# SLT3-PAY-1Q2T_P2.net
KiCad netlist of a schematic drawn in Altium Designer
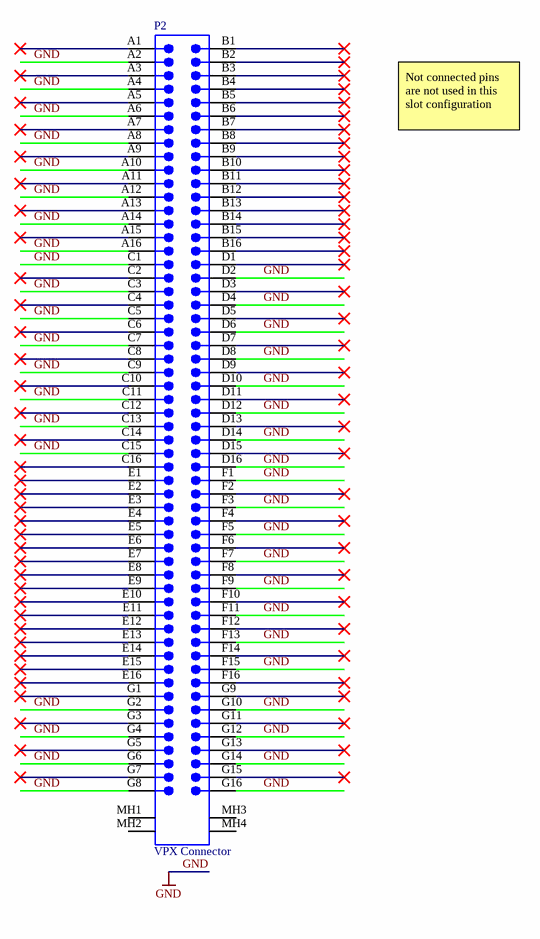
[diagram p0: SLT3-PAY-1Q2T_P2.SchDoc]

(export (version "E")
  (design (tool "Eeschema 10.0.6"))
  (components
    (comp (ref "P2")
      (value "VPX Connector")
      (footprint "BTB1-8-4H112M")
      (description "Ruggedized Board-to-Board Connector, Right Angle, 7-Row, Pitch 1.8mm, 112-Position")
      (fields (field (name "MANUFACTURER") "TE") (field (name "MANUFACTURER PART NUMBER") "2102771-1"))
      (libsource (lib "SVPX") (part "2102771-1"))
    )
  )
  (nets
    (net (code "1") (name "GND") (class "Default")
      (node (ref "P2") (pin "A10") (pinfunction "A10_A10") (pintype "passive"))
      (node (ref "P2") (pin "A12") (pinfunction "A12_A12") (pintype "passive"))
      (node (ref "P2") (pin "A14") (pinfunction "A14_A14") (pintype "passive"))
      (node (ref "P2") (pin "A16") (pinfunction "A16_A16") (pintype "passive"))
      (node (ref "P2") (pin "A2") (pinfunction "A2_A2") (pintype "passive"))
      (node (ref "P2") (pin "A4") (pinfunction "A4_A4") (pintype "passive"))
      (node (ref "P2") (pin "A6") (pinfunction "A6_A6") (pintype "passive"))
      (node (ref "P2") (pin "A8") (pinfunction "A8_A8") (pintype "passive"))
      (node (ref "P2") (pin "C1") (pinfunction "C1_C1") (pintype "passive"))
      (node (ref "P2") (pin "C11") (pinfunction "C11_C11") (pintype "passive"))
      (node (ref "P2") (pin "C13") (pinfunction "C13_C13") (pintype "passive"))
      (node (ref "P2") (pin "C15") (pinfunction "C15_C15") (pintype "passive"))
      (node (ref "P2") (pin "C3") (pinfunction "C3_C3") (pintype "passive"))
      (node (ref "P2") (pin "C5") (pinfunction "C5_C5") (pintype "passive"))
      (node (ref "P2") (pin "C7") (pinfunction "C7_C7") (pintype "passive"))
      (node (ref "P2") (pin "C9") (pinfunction "C9_C9") (pintype "passive"))
      (node (ref "P2") (pin "D10") (pinfunction "D10_D10") (pintype "passive"))
      (node (ref "P2") (pin "D12") (pinfunction "D12_D12") (pintype "passive"))
      (node (ref "P2") (pin "D14") (pinfunction "D14_D14") (pintype "passive"))
      (node (ref "P2") (pin "D16") (pinfunction "D16_D16") (pintype "passive"))
      (node (ref "P2") (pin "D2") (pinfunction "D2_D2") (pintype "passive"))
      (node (ref "P2") (pin "D4") (pinfunction "D4_D4") (pintype "passive"))
      (node (ref "P2") (pin "D6") (pinfunction "D6_D6") (pintype "passive"))
      (node (ref "P2") (pin "D8") (pinfunction "D8_D8") (pintype "passive"))
      (node (ref "P2") (pin "F1") (pinfunction "F1_F1") (pintype "passive"))
      (node (ref "P2") (pin "F11") (pinfunction "F11_F11") (pintype "passive"))
      (node (ref "P2") (pin "F13") (pinfunction "F13_F13") (pintype "passive"))
      (node (ref "P2") (pin "F15") (pinfunction "F15_F15") (pintype "passive"))
      (node (ref "P2") (pin "F3") (pinfunction "F3_F3") (pintype "passive"))
      (node (ref "P2") (pin "F5") (pinfunction "F5_F5") (pintype "passive"))
      (node (ref "P2") (pin "F7") (pinfunction "F7_F7") (pintype "passive"))
      (node (ref "P2") (pin "F9") (pinfunction "F9_F9") (pintype "passive"))
      (node (ref "P2") (pin "G10") (pinfunction "G10_G10") (pintype "passive"))
      (node (ref "P2") (pin "G12") (pinfunction "G12_G12") (pintype "passive"))
      (node (ref "P2") (pin "G14") (pinfunction "G14_G14") (pintype "passive"))
      (node (ref "P2") (pin "G16") (pinfunction "G16_G16") (pintype "passive"))
      (node (ref "P2") (pin "G2") (pinfunction "G2_G2") (pintype "passive"))
      (node (ref "P2") (pin "G4") (pinfunction "G4_G4") (pintype "passive"))
      (node (ref "P2") (pin "G6") (pinfunction "G6_G6") (pintype "passive"))
      (node (ref "P2") (pin "G8") (pinfunction "G8_G8") (pintype "passive"))
    )
    (net (code "2") (name "unconnected-(P2-PadA1)") (class "Default")
      (node (ref "P2") (pin "A1") (pinfunction "A1_A1") (pintype "passive+no_connect"))
    )
    (net (code "3") (name "unconnected-(P2-PadA3)") (class "Default")
      (node (ref "P2") (pin "A3") (pinfunction "A3_A3") (pintype "passive+no_connect"))
    )
    (net (code "4") (name "unconnected-(P2-PadA5)") (class "Default")
      (node (ref "P2") (pin "A5") (pinfunction "A5_A5") (pintype "passive+no_connect"))
    )
    (net (code "5") (name "unconnected-(P2-PadA7)") (class "Default")
      (node (ref "P2") (pin "A7") (pinfunction "A7_A7") (pintype "passive+no_connect"))
    )
    (net (code "6") (name "unconnected-(P2-PadA9)") (class "Default")
      (node (ref "P2") (pin "A9") (pinfunction "A9_A9") (pintype "passive+no_connect"))
    )
    (net (code "7") (name "unconnected-(P2-PadA11)") (class "Default")
      (node (ref "P2") (pin "A11") (pinfunction "A11_A11") (pintype "passive+no_connect"))
    )
    (net (code "8") (name "unconnected-(P2-PadA13)") (class "Default")
      (node (ref "P2") (pin "A13") (pinfunction "A13_A13") (pintype "passive+no_connect"))
    )
    (net (code "9") (name "unconnected-(P2-PadA15)") (class "Default")
      (node (ref "P2") (pin "A15") (pinfunction "A15_A15") (pintype "passive+no_connect"))
    )
    (net (code "10") (name "unconnected-(P2-PadB1)") (class "Default")
      (node (ref "P2") (pin "B1") (pinfunction "B1_B1") (pintype "passive+no_connect"))
    )
    (net (code "11") (name "unconnected-(P2-PadB2)") (class "Default")
      (node (ref "P2") (pin "B2") (pinfunction "B2_B2") (pintype "passive+no_connect"))
    )
    (net (code "12") (name "unconnected-(P2-PadB3)") (class "Default")
      (node (ref "P2") (pin "B3") (pinfunction "B3_B3") (pintype "passive+no_connect"))
    )
    (net (code "13") (name "unconnected-(P2-PadB4)") (class "Default")
      (node (ref "P2") (pin "B4") (pinfunction "B4_B4") (pintype "passive+no_connect"))
    )
    (net (code "14") (name "unconnected-(P2-PadB5)") (class "Default")
      (node (ref "P2") (pin "B5") (pinfunction "B5_B5") (pintype "passive+no_connect"))
    )
    (net (code "15") (name "unconnected-(P2-PadB6)") (class "Default")
      (node (ref "P2") (pin "B6") (pinfunction "B6_B6") (pintype "passive+no_connect"))
    )
    (net (code "16") (name "unconnected-(P2-PadB7)") (class "Default")
      (node (ref "P2") (pin "B7") (pinfunction "B7_B7") (pintype "passive+no_connect"))
    )
    (net (code "17") (name "unconnected-(P2-PadB8)") (class "Default")
      (node (ref "P2") (pin "B8") (pinfunction "B8_B8") (pintype "passive+no_connect"))
    )
    (net (code "18") (name "unconnected-(P2-PadB9)") (class "Default")
      (node (ref "P2") (pin "B9") (pinfunction "B9_B9") (pintype "passive+no_connect"))
    )
    (net (code "19") (name "unconnected-(P2-PadB10)") (class "Default")
      (node (ref "P2") (pin "B10") (pinfunction "B10_B10") (pintype "passive+no_connect"))
    )
    (net (code "20") (name "unconnected-(P2-PadB11)") (class "Default")
      (node (ref "P2") (pin "B11") (pinfunction "B11_B11") (pintype "passive+no_connect"))
    )
    (net (code "21") (name "unconnected-(P2-PadB12)") (class "Default")
      (node (ref "P2") (pin "B12") (pinfunction "B12_B12") (pintype "passive+no_connect"))
    )
    (net (code "22") (name "unconnected-(P2-PadB13)") (class "Default")
      (node (ref "P2") (pin "B13") (pinfunction "B13_B13") (pintype "passive+no_connect"))
    )
    (net (code "23") (name "unconnected-(P2-PadB14)") (class "Default")
      (node (ref "P2") (pin "B14") (pinfunction "B14_B14") (pintype "passive+no_connect"))
    )
    (net (code "24") (name "unconnected-(P2-PadB15)") (class "Default")
      (node (ref "P2") (pin "B15") (pinfunction "B15_B15") (pintype "passive+no_connect"))
    )
    (net (code "25") (name "unconnected-(P2-PadB16)") (class "Default")
      (node (ref "P2") (pin "B16") (pinfunction "B16_B16") (pintype "passive+no_connect"))
    )
    (net (code "26") (name "unconnected-(P2-PadC2)") (class "Default")
      (node (ref "P2") (pin "C2") (pinfunction "C2_C2") (pintype "passive+no_connect"))
    )
    (net (code "27") (name "unconnected-(P2-PadC4)") (class "Default")
      (node (ref "P2") (pin "C4") (pinfunction "C4_C4") (pintype "passive+no_connect"))
    )
    (net (code "28") (name "unconnected-(P2-PadC6)") (class "Default")
      (node (ref "P2") (pin "C6") (pinfunction "C6_C6") (pintype "passive+no_connect"))
    )
    (net (code "29") (name "unconnected-(P2-PadC8)") (class "Default")
      (node (ref "P2") (pin "C8") (pinfunction "C8_C8") (pintype "passive+no_connect"))
    )
    (net (code "30") (name "unconnected-(P2-PadC10)") (class "Default")
      (node (ref "P2") (pin "C10") (pinfunction "C10_C10") (pintype "passive+no_connect"))
    )
    (net (code "31") (name "unconnected-(P2-PadC12)") (class "Default")
      (node (ref "P2") (pin "C12") (pinfunction "C12_C12") (pintype "passive+no_connect"))
    )
    (net (code "32") (name "unconnected-(P2-PadC14)") (class "Default")
      (node (ref "P2") (pin "C14") (pinfunction "C14_C14") (pintype "passive+no_connect"))
    )
    (net (code "33") (name "unconnected-(P2-PadC16)") (class "Default")
      (node (ref "P2") (pin "C16") (pinfunction "C16_C16") (pintype "passive+no_connect"))
    )
    (net (code "34") (name "unconnected-(P2-PadD1)") (class "Default")
      (node (ref "P2") (pin "D1") (pinfunction "D1_D1") (pintype "passive+no_connect"))
    )
    (net (code "35") (name "unconnected-(P2-PadD3)") (class "Default")
      (node (ref "P2") (pin "D3") (pinfunction "D3_D3") (pintype "passive+no_connect"))
    )
    (net (code "36") (name "unconnected-(P2-PadD5)") (class "Default")
      (node (ref "P2") (pin "D5") (pinfunction "D5_D5") (pintype "passive+no_connect"))
    )
    (net (code "37") (name "unconnected-(P2-PadD7)") (class "Default")
      (node (ref "P2") (pin "D7") (pinfunction "D7_D7") (pintype "passive+no_connect"))
    )
    (net (code "38") (name "unconnected-(P2-PadD9)") (class "Default")
      (node (ref "P2") (pin "D9") (pinfunction "D9_D9") (pintype "passive+no_connect"))
    )
    (net (code "39") (name "unconnected-(P2-PadD11)") (class "Default")
      (node (ref "P2") (pin "D11") (pinfunction "D11_D11") (pintype "passive+no_connect"))
    )
    (net (code "40") (name "unconnected-(P2-PadD13)") (class "Default")
      (node (ref "P2") (pin "D13") (pinfunction "D13_D13") (pintype "passive+no_connect"))
    )
    (net (code "41") (name "unconnected-(P2-PadD15)") (class "Default")
      (node (ref "P2") (pin "D15") (pinfunction "D15_D15") (pintype "passive+no_connect"))
    )
    (net (code "42") (name "unconnected-(P2-PadE1)") (class "Default")
      (node (ref "P2") (pin "E1") (pinfunction "E1_E1") (pintype "passive+no_connect"))
    )
    (net (code "43") (name "unconnected-(P2-PadE2)") (class "Default")
      (node (ref "P2") (pin "E2") (pinfunction "E2_E2") (pintype "passive+no_connect"))
    )
    (net (code "44") (name "unconnected-(P2-PadE3)") (class "Default")
      (node (ref "P2") (pin "E3") (pinfunction "E3_E3") (pintype "passive+no_connect"))
    )
    (net (code "45") (name "unconnected-(P2-PadE4)") (class "Default")
      (node (ref "P2") (pin "E4") (pinfunction "E4_E4") (pintype "passive+no_connect"))
    )
    (net (code "46") (name "unconnected-(P2-PadE5)") (class "Default")
      (node (ref "P2") (pin "E5") (pinfunction "E5_E5") (pintype "passive+no_connect"))
    )
    (net (code "47") (name "unconnected-(P2-PadE6)") (class "Default")
      (node (ref "P2") (pin "E6") (pinfunction "E6_E6") (pintype "passive+no_connect"))
    )
    (net (code "48") (name "unconnected-(P2-PadE7)") (class "Default")
      (node (ref "P2") (pin "E7") (pinfunction "E7_E7") (pintype "passive+no_connect"))
    )
    (net (code "49") (name "unconnected-(P2-PadE8)") (class "Default")
      (node (ref "P2") (pin "E8") (pinfunction "E8_E8") (pintype "passive+no_connect"))
    )
    (net (code "50") (name "unconnected-(P2-PadE9)") (class "Default")
      (node (ref "P2") (pin "E9") (pinfunction "E9_E9") (pintype "passive+no_connect"))
    )
    (net (code "51") (name "unconnected-(P2-PadE10)") (class "Default")
      (node (ref "P2") (pin "E10") (pinfunction "E10_E10") (pintype "passive+no_connect"))
    )
    (net (code "52") (name "unconnected-(P2-PadE11)") (class "Default")
      (node (ref "P2") (pin "E11") (pinfunction "E11_E11") (pintype "passive+no_connect"))
    )
    (net (code "53") (name "unconnected-(P2-PadE12)") (class "Default")
      (node (ref "P2") (pin "E12") (pinfunction "E12_E12") (pintype "passive+no_connect"))
    )
    (net (code "54") (name "unconnected-(P2-PadE13)") (class "Default")
      (node (ref "P2") (pin "E13") (pinfunction "E13_E13") (pintype "passive+no_connect"))
    )
    (net (code "55") (name "unconnected-(P2-PadE14)") (class "Default")
      (node (ref "P2") (pin "E14") (pinfunction "E14_E14") (pintype "passive+no_connect"))
    )
    (net (code "56") (name "unconnected-(P2-PadE15)") (class "Default")
      (node (ref "P2") (pin "E15") (pinfunction "E15_E15") (pintype "passive+no_connect"))
    )
    (net (code "57") (name "unconnected-(P2-PadE16)") (class "Default")
      (node (ref "P2") (pin "E16") (pinfunction "E16_E16") (pintype "passive+no_connect"))
    )
    (net (code "58") (name "unconnected-(P2-PadF2)") (class "Default")
      (node (ref "P2") (pin "F2") (pinfunction "F2_F2") (pintype "passive+no_connect"))
    )
    (net (code "59") (name "unconnected-(P2-PadF4)") (class "Default")
      (node (ref "P2") (pin "F4") (pinfunction "F4_F4") (pintype "passive+no_connect"))
    )
    (net (code "60") (name "unconnected-(P2-PadF6)") (class "Default")
      (node (ref "P2") (pin "F6") (pinfunction "F6_F6") (pintype "passive+no_connect"))
    )
    (net (code "61") (name "unconnected-(P2-PadF8)") (class "Default")
      (node (ref "P2") (pin "F8") (pinfunction "F8_F8") (pintype "passive+no_connect"))
    )
    (net (code "62") (name "unconnected-(P2-PadF10)") (class "Default")
      (node (ref "P2") (pin "F10") (pinfunction "F10_F10") (pintype "passive+no_connect"))
    )
    (net (code "63") (name "unconnected-(P2-PadF12)") (class "Default")
      (node (ref "P2") (pin "F12") (pinfunction "F12_F12") (pintype "passive+no_connect"))
    )
    (net (code "64") (name "unconnected-(P2-PadF14)") (class "Default")
      (node (ref "P2") (pin "F14") (pinfunction "F14_F14") (pintype "passive+no_connect"))
    )
    (net (code "65") (name "unconnected-(P2-PadF16)") (class "Default")
      (node (ref "P2") (pin "F16") (pinfunction "F16_F16") (pintype "passive+no_connect"))
    )
    (net (code "66") (name "unconnected-(P2-PadG1)") (class "Default")
      (node (ref "P2") (pin "G1") (pinfunction "G1_G1") (pintype "passive+no_connect"))
    )
    (net (code "67") (name "unconnected-(P2-PadG3)") (class "Default")
      (node (ref "P2") (pin "G3") (pinfunction "G3_G3") (pintype "passive+no_connect"))
    )
    (net (code "68") (name "unconnected-(P2-PadG5)") (class "Default")
      (node (ref "P2") (pin "G5") (pinfunction "G5_G5") (pintype "passive+no_connect"))
    )
    (net (code "69") (name "unconnected-(P2-PadG7)") (class "Default")
      (node (ref "P2") (pin "G7") (pinfunction "G7_G7") (pintype "passive+no_connect"))
    )
    (net (code "70") (name "unconnected-(P2-PadG9)") (class "Default")
      (node (ref "P2") (pin "G9") (pinfunction "G9_G9") (pintype "passive+no_connect"))
    )
    (net (code "71") (name "unconnected-(P2-PadG11)") (class "Default")
      (node (ref "P2") (pin "G11") (pinfunction "G11_G11") (pintype "passive+no_connect"))
    )
    (net (code "72") (name "unconnected-(P2-PadG13)") (class "Default")
      (node (ref "P2") (pin "G13") (pinfunction "G13_G13") (pintype "passive+no_connect"))
    )
    (net (code "73") (name "unconnected-(P2-PadG15)") (class "Default")
      (node (ref "P2") (pin "G15") (pinfunction "G15_G15") (pintype "passive+no_connect"))
    )
    (net (code "74") (name "unconnected-(P2-PadMH1)") (class "Default")
      (node (ref "P2") (pin "MH1") (pinfunction "MH1_MH1") (pintype "passive"))
    )
    (net (code "75") (name "unconnected-(P2-PadMH2)") (class "Default")
      (node (ref "P2") (pin "MH2") (pinfunction "MH2_MH2") (pintype "passive"))
    )
    (net (code "76") (name "unconnected-(P2-PadMH3)") (class "Default")
      (node (ref "P2") (pin "MH3") (pinfunction "MH3_MH3") (pintype "passive"))
    )
    (net (code "77") (name "unconnected-(P2-PadMH4)") (class "Default")
      (node (ref "P2") (pin "MH4") (pinfunction "MH4_MH4") (pintype "passive"))
    )
  )
)
